# Logic_board.net
KiCad netlist of a schematic drawn in EAGLE
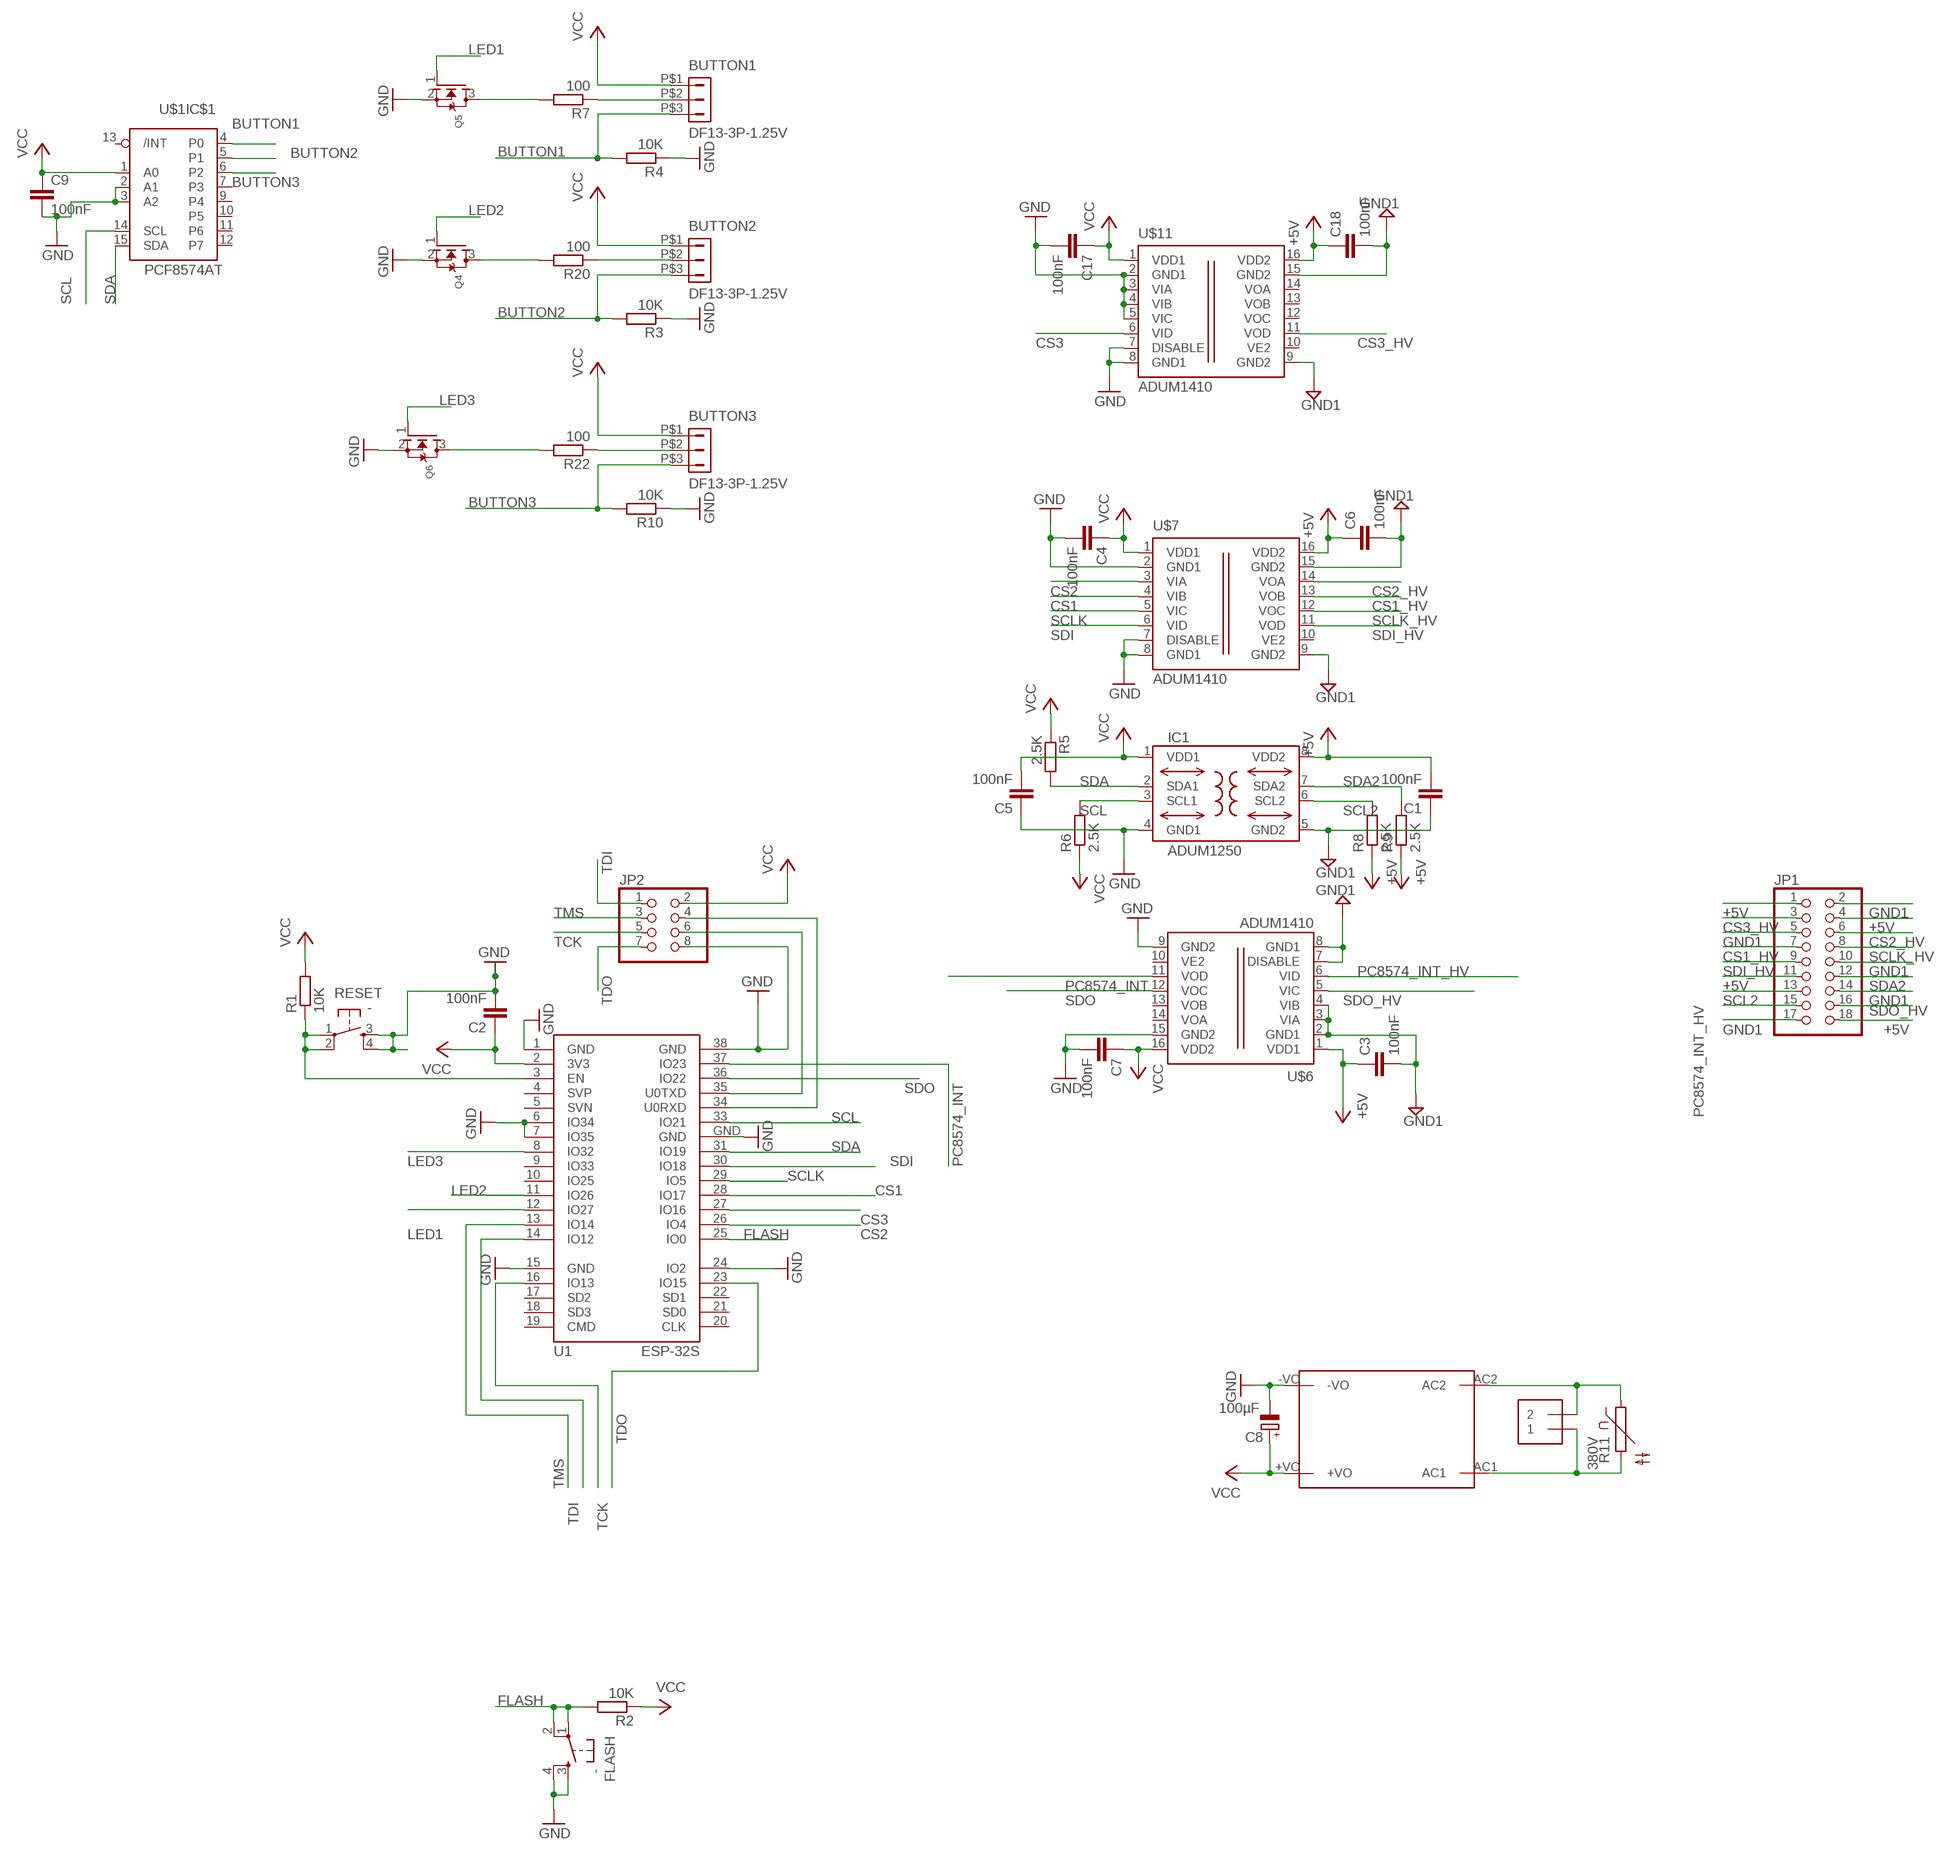
[diagram p0: schematic, sheet 1]

(export (version "E")
  (design (tool "Eeschema 10.0.6"))
  (components
    (comp (ref "BUTTON1")
      (value "DF13-3P-1.25V")
      (footprint "eagle-import:DF13C-3P-1.25V")
      (libsource (lib "eagle-import") (part "DF13-3P-1.25V"))
    )
    (comp (ref "BUTTON2")
      (value "DF13-3P-1.25V")
      (footprint "eagle-import:DF13C-3P-1.25V")
      (libsource (lib "eagle-import") (part "DF13-3P-1.25V"))
    )
    (comp (ref "BUTTON3")
      (value "DF13-3P-1.25V")
      (footprint "eagle-import:DF13C-3P-1.25V")
      (libsource (lib "eagle-import") (part "DF13-3P-1.25V"))
    )
    (comp (ref "C1")
      (value "100nF")
      (footprint "eagle-import:C0805")
      (libsource (lib "eagle-import") (part "C-EUC0805"))
    )
    (comp (ref "C2")
      (value "100nF")
      (footprint "eagle-import:C0805")
      (libsource (lib "eagle-import") (part "C-EUC0805"))
    )
    (comp (ref "C3")
      (value "100nF")
      (footprint "eagle-import:C0805")
      (libsource (lib "eagle-import") (part "C-EUC0805"))
    )
    (comp (ref "C4")
      (value "100nF")
      (footprint "eagle-import:C0805")
      (libsource (lib "eagle-import") (part "C-EUC0805"))
    )
    (comp (ref "C5")
      (value "100nF")
      (footprint "eagle-import:C0805")
      (libsource (lib "eagle-import") (part "C-EUC0805"))
    )
    (comp (ref "C6")
      (value "100nF")
      (footprint "eagle-import:C0805")
      (libsource (lib "eagle-import") (part "C-EUC0805"))
    )
    (comp (ref "C7")
      (value "100nF")
      (footprint "eagle-import:C0805")
      (libsource (lib "eagle-import") (part "C-EUC0805"))
    )
    (comp (ref "C8")
      (value "100µF")
      (footprint "eagle-import:E2,5-6")
      (libsource (lib "eagle-import") (part "CPOL-EUE2.5-6"))
    )
    (comp (ref "C9")
      (value "100nF")
      (footprint "eagle-import:C0805")
      (libsource (lib "eagle-import") (part "C-EUC0805"))
    )
    (comp (ref "C17")
      (value "100nF")
      (footprint "eagle-import:C0805")
      (libsource (lib "eagle-import") (part "C-EUC0805"))
    )
    (comp (ref "C18")
      (value "100nF")
      (footprint "eagle-import:C0805")
      (libsource (lib "eagle-import") (part "C-EUC0805"))
    )
    (comp (ref "FLASH")
      (value "-")
      (footprint "eagle-import:DTSM-6")
      (libsource (lib "eagle-import") (part "DTSM-6"))
    )
    (comp (ref "IC1")
      (value "ADUM1250")
      (footprint "eagle-import:SO8-COOL")
      (libsource (lib "eagle-import") (part "ADUM1250"))
    )
    (comp (ref "J1")
      (value "1X2-3.5MM")
      (footprint "eagle-import:1X2-3.5MM")
      (libsource (lib "eagle-import") (part "1X2-3.5MM"))
    )
    (comp (ref "JP1")
      (value "PINHD-2X9")
      (footprint "eagle-import:2X09")
      (libsource (lib "eagle-import") (part "PINHD-2X9"))
    )
    (comp (ref "JP2")
      (value "PINHD-2X4")
      (footprint "eagle-import:2X04")
      (libsource (lib "eagle-import") (part "PINHD-2X4"))
    )
    (comp (ref "Q4")
      (value "MOSFET-NREFLOW")
      (footprint "eagle-import:SOT23")
      (libsource (lib "eagle-import") (part "MOSFET-NREFLOW"))
    )
    (comp (ref "Q5")
      (value "MOSFET-NREFLOW")
      (footprint "eagle-import:SOT23")
      (libsource (lib "eagle-import") (part "MOSFET-NREFLOW"))
    )
    (comp (ref "Q6")
      (value "MOSFET-NREFLOW")
      (footprint "eagle-import:SOT23")
      (libsource (lib "eagle-import") (part "MOSFET-NREFLOW"))
    )
    (comp (ref "R1")
      (value "10K")
      (footprint "eagle-import:R0805")
      (libsource (lib "eagle-import") (part "R-EU_R0805"))
    )
    (comp (ref "R2")
      (value "10K")
      (footprint "eagle-import:R0805")
      (libsource (lib "eagle-import") (part "R-EU_R0805"))
    )
    (comp (ref "R3")
      (value "10K")
      (footprint "eagle-import:R0805")
      (libsource (lib "eagle-import") (part "R-EU_R0805"))
    )
    (comp (ref "R4")
      (value "10K")
      (footprint "eagle-import:R0805")
      (libsource (lib "eagle-import") (part "R-EU_R0805"))
    )
    (comp (ref "R5")
      (value "2.5K")
      (footprint "eagle-import:R0805")
      (libsource (lib "eagle-import") (part "R-EU_R0805"))
    )
    (comp (ref "R6")
      (value "2.5K")
      (footprint "eagle-import:R0805")
      (libsource (lib "eagle-import") (part "R-EU_R0805"))
    )
    (comp (ref "R7")
      (value "100")
      (footprint "eagle-import:R0805")
      (libsource (lib "eagle-import") (part "R-EU_R0805"))
    )
    (comp (ref "R8")
      (value "2.5K")
      (footprint "eagle-import:R0805")
      (libsource (lib "eagle-import") (part "R-EU_R0805"))
    )
    (comp (ref "R9")
      (value "2.5K")
      (footprint "eagle-import:R0805")
      (libsource (lib "eagle-import") (part "R-EU_R0805"))
    )
    (comp (ref "R10")
      (value "10K")
      (footprint "eagle-import:R0805")
      (libsource (lib "eagle-import") (part "R-EU_R0805"))
    )
    (comp (ref "R11")
      (value "380V")
      (footprint "eagle-import:S14K11")
      (libsource (lib "eagle-import") (part "S14K11"))
    )
    (comp (ref "R20")
      (value "100")
      (footprint "eagle-import:R0805")
      (libsource (lib "eagle-import") (part "R-EU_R0805"))
    )
    (comp (ref "R22")
      (value "100")
      (footprint "eagle-import:R0805")
      (libsource (lib "eagle-import") (part "R-EU_R0805"))
    )
    (comp (ref "RESET")
      (value "-")
      (footprint "eagle-import:DTSM-6")
      (libsource (lib "eagle-import") (part "DTSM-6"))
    )
    (comp (ref "SUPPLY")
      (value "5V")
      (footprint "eagle-import:HLK-PM03")
      (libsource (lib "eagle-import") (part "HLK-PM03"))
    )
    (comp (ref "U$1")
      (value "PCF8574AT")
      (footprint "eagle-import:SO16")
      (libsource (lib "eagle-import") (part "PCF8574AT"))
    )
    (comp (ref "U$6")
      (value "ADUM1410")
      (footprint "eagle-import:SOIC-16")
      (libsource (lib "eagle-import") (part "ADUM1410"))
    )
    (comp (ref "U$7")
      (value "ADUM1410")
      (footprint "eagle-import:SOIC-16")
      (libsource (lib "eagle-import") (part "ADUM1410"))
    )
    (comp (ref "U$11")
      (value "ADUM1410")
      (footprint "eagle-import:SOIC-16")
      (libsource (lib "eagle-import") (part "ADUM1410"))
    )
    (comp (ref "U1")
      (value "ESP-32S")
      (footprint "eagle-import:ESP-32S")
      (libsource (lib "eagle-import") (part "ESP-32S"))
    )
  )
  (nets
    (net (code "1") (name "+5V") (class "Default")
      (node (ref "C1") (pin "2") (pinfunction "2_2") (pintype "passive"))
      (node (ref "C18") (pin "1") (pinfunction "1_1") (pintype "passive"))
      (node (ref "C3") (pin "1") (pinfunction "1_1") (pintype "passive"))
      (node (ref "C6") (pin "1") (pinfunction "1_1") (pintype "passive"))
      (node (ref "IC1") (pin "8") (pinfunction "VDD2_8") (pintype "power_in"))
      (node (ref "JP1") (pin "1") (pinfunction "1_1") (pintype "passive"))
      (node (ref "JP1") (pin "11") (pinfunction "11_11") (pintype "passive"))
      (node (ref "JP1") (pin "18") (pinfunction "18_18") (pintype "passive"))
      (node (ref "JP1") (pin "4") (pinfunction "4_4") (pintype "passive"))
      (node (ref "R8") (pin "1") (pinfunction "1_1") (pintype "passive"))
      (node (ref "R9") (pin "1") (pinfunction "1_1") (pintype "passive"))
      (node (ref "U$11") (pin "16") (pinfunction "VDD2_16") (pintype "input"))
      (node (ref "U$6") (pin "1") (pinfunction "VDD1_1") (pintype "input"))
      (node (ref "U$7") (pin "16") (pinfunction "VDD2_16") (pintype "input"))
    )
    (net (code "2") (name "/BUTTON1") (class "Default")
      (node (ref "BUTTON1") (pin "P$3") (pinfunction "3_P$3") (pintype "passive"))
      (node (ref "R4") (pin "2") (pinfunction "2_2") (pintype "passive"))
      (node (ref "U$1") (pin "4") (pinfunction "P0_4") (pintype "bidirectional"))
    )
    (net (code "3") (name "/BUTTON2") (class "Default")
      (node (ref "BUTTON2") (pin "P$3") (pinfunction "3_P$3") (pintype "passive"))
      (node (ref "R3") (pin "2") (pinfunction "2_2") (pintype "passive"))
      (node (ref "U$1") (pin "5") (pinfunction "P1_5") (pintype "bidirectional"))
    )
    (net (code "4") (name "/BUTTON3") (class "Default")
      (node (ref "BUTTON3") (pin "P$3") (pinfunction "3_P$3") (pintype "passive"))
      (node (ref "R10") (pin "2") (pinfunction "2_2") (pintype "passive"))
      (node (ref "U$1") (pin "6") (pinfunction "P2_6") (pintype "bidirectional"))
    )
    (net (code "5") (name "/CS1") (class "Default")
      (node (ref "U$7") (pin "4") (pinfunction "VIB_4") (pintype "input"))
      (node (ref "U1") (pin "28") (pinfunction "IO17_28") (pintype "bidirectional"))
    )
    (net (code "6") (name "/CS1_HV") (class "Default")
      (node (ref "JP1") (pin "7") (pinfunction "7_7") (pintype "passive"))
      (node (ref "U$7") (pin "13") (pinfunction "VOB_13") (pintype "tri_state"))
    )
    (net (code "7") (name "/CS2") (class "Default")
      (node (ref "U$7") (pin "3") (pinfunction "VIA_3") (pintype "input"))
      (node (ref "U1") (pin "26") (pinfunction "IO4_26") (pintype "bidirectional"))
    )
    (net (code "8") (name "/CS2_HV") (class "Default")
      (node (ref "JP1") (pin "6") (pinfunction "6_6") (pintype "passive"))
      (node (ref "U$7") (pin "14") (pinfunction "VOA_14") (pintype "tri_state"))
    )
    (net (code "9") (name "/CS3") (class "Default")
      (node (ref "U$11") (pin "6") (pinfunction "VID_6") (pintype "input"))
      (node (ref "U1") (pin "27") (pinfunction "IO16_27") (pintype "bidirectional"))
    )
    (net (code "10") (name "/CS3_HV") (class "Default")
      (node (ref "JP1") (pin "3") (pinfunction "3_3") (pintype "passive"))
      (node (ref "U$11") (pin "11") (pinfunction "VOD_11") (pintype "tri_state"))
    )
    (net (code "11") (name "/FLASH") (class "Default")
      (node (ref "FLASH") (pin "1") (pinfunction "1_1") (pintype "passive"))
      (node (ref "FLASH") (pin "2") (pinfunction "2_2") (pintype "passive"))
      (node (ref "R2") (pin "2") (pinfunction "2_2") (pintype "passive"))
      (node (ref "U1") (pin "25") (pinfunction "IO0_25") (pintype "bidirectional"))
    )
    (net (code "12") (name "/LED1") (class "Default")
      (node (ref "Q5") (pin "1") (pinfunction "G_1") (pintype "bidirectional"))
      (node (ref "U1") (pin "12") (pinfunction "IO27_12") (pintype "bidirectional"))
    )
    (net (code "13") (name "/LED2") (class "Default")
      (node (ref "Q4") (pin "1") (pinfunction "G_1") (pintype "bidirectional"))
      (node (ref "U1") (pin "11") (pinfunction "IO26_11") (pintype "bidirectional"))
    )
    (net (code "14") (name "/LED3") (class "Default")
      (node (ref "Q6") (pin "1") (pinfunction "G_1") (pintype "bidirectional"))
      (node (ref "U1") (pin "8") (pinfunction "IO32_8") (pintype "bidirectional"))
    )
    (net (code "15") (name "/PC8574_INT") (class "Default")
      (node (ref "U$6") (pin "11") (pinfunction "VOD_11") (pintype "tri_state"))
      (node (ref "U1") (pin "37") (pinfunction "IO23_37") (pintype "bidirectional"))
    )
    (net (code "16") (name "/PC8574_INT_HV") (class "Default")
      (node (ref "JP1") (pin "15") (pinfunction "15_15") (pintype "passive"))
      (node (ref "U$6") (pin "6") (pinfunction "VID_6") (pintype "input"))
    )
    (net (code "17") (name "/SCL") (class "Default")
      (node (ref "IC1") (pin "3") (pinfunction "SCL1_3") (pintype "bidirectional"))
      (node (ref "R6") (pin "2") (pinfunction "2_2") (pintype "passive"))
      (node (ref "U$1") (pin "14") (pinfunction "SCL_14") (pintype "input"))
      (node (ref "U1") (pin "33") (pinfunction "IO21_33") (pintype "bidirectional"))
    )
    (net (code "18") (name "/SCL2") (class "Default")
      (node (ref "IC1") (pin "6") (pinfunction "SCL2_6") (pintype "bidirectional"))
      (node (ref "JP1") (pin "13") (pinfunction "13_13") (pintype "passive"))
      (node (ref "R8") (pin "2") (pinfunction "2_2") (pintype "passive"))
    )
    (net (code "19") (name "/SCLK") (class "Default")
      (node (ref "U$7") (pin "5") (pinfunction "VIC_5") (pintype "input"))
      (node (ref "U1") (pin "29") (pinfunction "IO5_29") (pintype "bidirectional"))
    )
    (net (code "20") (name "/SCLK_HV") (class "Default")
      (node (ref "JP1") (pin "8") (pinfunction "8_8") (pintype "passive"))
      (node (ref "U$7") (pin "12") (pinfunction "VOC_12") (pintype "tri_state"))
    )
    (net (code "21") (name "/SDA") (class "Default")
      (node (ref "IC1") (pin "2") (pinfunction "SDA1_2") (pintype "bidirectional"))
      (node (ref "R5") (pin "2") (pinfunction "2_2") (pintype "passive"))
      (node (ref "U$1") (pin "15") (pinfunction "SDA_15") (pintype "bidirectional"))
      (node (ref "U1") (pin "31") (pinfunction "IO19_31") (pintype "bidirectional"))
    )
    (net (code "22") (name "/SDA2") (class "Default")
      (node (ref "IC1") (pin "7") (pinfunction "SDA2_7") (pintype "bidirectional"))
      (node (ref "JP1") (pin "12") (pinfunction "12_12") (pintype "passive"))
      (node (ref "R9") (pin "2") (pinfunction "2_2") (pintype "passive"))
    )
    (net (code "23") (name "/SDI") (class "Default")
      (node (ref "U$7") (pin "6") (pinfunction "VID_6") (pintype "input"))
      (node (ref "U1") (pin "30") (pinfunction "IO18_30") (pintype "bidirectional"))
    )
    (net (code "24") (name "/SDI_HV") (class "Default")
      (node (ref "JP1") (pin "9") (pinfunction "9_9") (pintype "passive"))
      (node (ref "U$7") (pin "11") (pinfunction "VOD_11") (pintype "tri_state"))
    )
    (net (code "25") (name "/SDO") (class "Default")
      (node (ref "U$6") (pin "12") (pinfunction "VOC_12") (pintype "tri_state"))
      (node (ref "U1") (pin "36") (pinfunction "IO22_36") (pintype "bidirectional"))
    )
    (net (code "26") (name "/SDO_HV") (class "Default")
      (node (ref "JP1") (pin "16") (pinfunction "16_16") (pintype "passive"))
      (node (ref "U$6") (pin "5") (pinfunction "VIC_5") (pintype "input"))
    )
    (net (code "27") (name "/TCK") (class "Default")
      (node (ref "JP2") (pin "5") (pinfunction "5_5") (pintype "passive"))
      (node (ref "U1") (pin "16") (pinfunction "IO13_16") (pintype "bidirectional"))
    )
    (net (code "28") (name "/TDI") (class "Default")
      (node (ref "JP2") (pin "1") (pinfunction "1_1") (pintype "passive"))
      (node (ref "U1") (pin "14") (pinfunction "IO12_14") (pintype "bidirectional"))
    )
    (net (code "29") (name "/TDO") (class "Default")
      (node (ref "JP2") (pin "7") (pinfunction "7_7") (pintype "passive"))
      (node (ref "U1") (pin "23") (pinfunction "IO15_23") (pintype "bidirectional"))
    )
    (net (code "30") (name "/TMS") (class "Default")
      (node (ref "JP2") (pin "3") (pinfunction "3_3") (pintype "passive"))
      (node (ref "U1") (pin "13") (pinfunction "IO14_13") (pintype "bidirectional"))
    )
    (net (code "31") (name "GND") (class "Default")
      (node (ref "C17") (pin "2") (pinfunction "2_2") (pintype "passive"))
      (node (ref "C2") (pin "2") (pinfunction "2_2") (pintype "passive"))
      (node (ref "C4") (pin "2") (pinfunction "2_2") (pintype "passive"))
      (node (ref "C5") (pin "1") (pinfunction "1_1") (pintype "passive"))
      (node (ref "C7") (pin "2") (pinfunction "2_2") (pintype "passive"))
      (node (ref "C8") (pin "-") (pinfunction "-_-") (pintype "passive"))
      (node (ref "C9") (pin "2") (pinfunction "2_2") (pintype "passive"))
      (node (ref "FLASH") (pin "3") (pinfunction "3_3") (pintype "passive"))
      (node (ref "FLASH") (pin "4") (pinfunction "4_4") (pintype "passive"))
      (node (ref "IC1") (pin "4") (pinfunction "GND1_4") (pintype "power_in"))
      (node (ref "JP2") (pin "8") (pinfunction "8_8") (pintype "passive"))
      (node (ref "Q4") (pin "2") (pinfunction "S_2") (pintype "bidirectional"))
      (node (ref "Q5") (pin "2") (pinfunction "S_2") (pintype "bidirectional"))
      (node (ref "Q6") (pin "2") (pinfunction "S_2") (pintype "bidirectional"))
      (node (ref "R10") (pin "1") (pinfunction "1_1") (pintype "passive"))
      (node (ref "R3") (pin "1") (pinfunction "1_1") (pintype "passive"))
      (node (ref "R4") (pin "1") (pinfunction "1_1") (pintype "passive"))
      (node (ref "RESET") (pin "3") (pinfunction "3_3") (pintype "passive"))
      (node (ref "RESET") (pin "4") (pinfunction "4_4") (pintype "passive"))
      (node (ref "SUPPLY") (pin "-VO") (pinfunction "-VO_-VO") (pintype "bidirectional"))
      (node (ref "U$1") (pin "2") (pinfunction "A1_2") (pintype "input"))
      (node (ref "U$1") (pin "3") (pinfunction "A2_3") (pintype "input"))
      (node (ref "U$11") (pin "2") (pinfunction "GND1_2") (pintype "input"))
      (node (ref "U$11") (pin "3") (pinfunction "VIA_3") (pintype "input"))
      (node (ref "U$11") (pin "4") (pinfunction "VIB_4") (pintype "input"))
      (node (ref "U$11") (pin "5") (pinfunction "VIC_5") (pintype "input"))
      (node (ref "U$11") (pin "7") (pinfunction "DISABLE_7") (pintype "input"))
      (node (ref "U$11") (pin "8") (pinfunction "GND1_8") (pintype "input"))
      (node (ref "U$6") (pin "15") (pinfunction "GND2_15") (pintype "input"))
      (node (ref "U$6") (pin "9") (pinfunction "GND2_9") (pintype "input"))
      (node (ref "U$7") (pin "2") (pinfunction "GND1_2") (pintype "input"))
      (node (ref "U$7") (pin "7") (pinfunction "DISABLE_7") (pintype "input"))
      (node (ref "U$7") (pin "8") (pinfunction "GND1_8") (pintype "input"))
      (node (ref "U1") (pin "1") (pinfunction "GND_1") (pintype "power_in"))
      (node (ref "U1") (pin "15") (pinfunction "GND_15") (pintype "power_in"))
      (node (ref "U1") (pin "24") (pinfunction "IO2_24") (pintype "bidirectional"))
      (node (ref "U1") (pin "38") (pinfunction "GND_38") (pintype "power_in"))
      (node (ref "U1") (pin "6") (pinfunction "IO34_6") (pintype "bidirectional"))
      (node (ref "U1") (pin "7") (pinfunction "IO35_7") (pintype "bidirectional"))
      (node (ref "U1") (pin "GND") (pinfunction "GND_GND") (pintype "power_in"))
    )
    (net (code "32") (name "GND1") (class "Default")
      (node (ref "C1") (pin "1") (pinfunction "1_1") (pintype "passive"))
      (node (ref "C18") (pin "2") (pinfunction "2_2") (pintype "passive"))
      (node (ref "C3") (pin "2") (pinfunction "2_2") (pintype "passive"))
      (node (ref "C6") (pin "2") (pinfunction "2_2") (pintype "passive"))
      (node (ref "IC1") (pin "5") (pinfunction "GND2_5") (pintype "power_in"))
      (node (ref "JP1") (pin "10") (pinfunction "10_10") (pintype "passive"))
      (node (ref "JP1") (pin "14") (pinfunction "14_14") (pintype "passive"))
      (node (ref "JP1") (pin "17") (pinfunction "17_17") (pintype "passive"))
      (node (ref "JP1") (pin "2") (pinfunction "2_2") (pintype "passive"))
      (node (ref "JP1") (pin "5") (pinfunction "5_5") (pintype "passive"))
      (node (ref "U$11") (pin "15") (pinfunction "GND2_15") (pintype "input"))
      (node (ref "U$11") (pin "9") (pinfunction "GND2_9") (pintype "input"))
      (node (ref "U$6") (pin "2") (pinfunction "GND1_2") (pintype "input"))
      (node (ref "U$6") (pin "3") (pinfunction "VIA_3") (pintype "input"))
      (node (ref "U$6") (pin "4") (pinfunction "VIB_4") (pintype "input"))
      (node (ref "U$6") (pin "7") (pinfunction "DISABLE_7") (pintype "input"))
      (node (ref "U$6") (pin "8") (pinfunction "GND1_8") (pintype "input"))
      (node (ref "U$7") (pin "15") (pinfunction "GND2_15") (pintype "input"))
      (node (ref "U$7") (pin "9") (pinfunction "GND2_9") (pintype "input"))
    )
    (net (code "33") (name "Net-(BUTTON1-2)") (class "Default")
      (node (ref "BUTTON1") (pin "P$2") (pinfunction "2_P$2") (pintype "passive"))
      (node (ref "R7") (pin "1") (pinfunction "1_1") (pintype "passive"))
    )
    (net (code "34") (name "Net-(BUTTON2-2)") (class "Default")
      (node (ref "BUTTON2") (pin "P$2") (pinfunction "2_P$2") (pintype "passive"))
      (node (ref "R20") (pin "1") (pinfunction "1_1") (pintype "passive"))
    )
    (net (code "35") (name "Net-(BUTTON3-2)") (class "Default")
      (node (ref "BUTTON3") (pin "P$2") (pinfunction "2_P$2") (pintype "passive"))
      (node (ref "R22") (pin "1") (pinfunction "1_1") (pintype "passive"))
    )
    (net (code "36") (name "Net-(J1-Pad1)") (class "Default")
      (node (ref "J1") (pin "1") (pinfunction "1_1") (pintype "passive"))
      (node (ref "R11") (pin "2") (pinfunction "2_2") (pintype "passive"))
      (node (ref "SUPPLY") (pin "AC1") (pinfunction "AC1_AC1") (pintype "bidirectional"))
    )
    (net (code "37") (name "Net-(J1-Pad2)") (class "Default")
      (node (ref "J1") (pin "2") (pinfunction "2_2") (pintype "passive"))
      (node (ref "R11") (pin "1") (pinfunction "1_1") (pintype "passive"))
      (node (ref "SUPPLY") (pin "AC2") (pinfunction "AC2_AC2") (pintype "bidirectional"))
    )
    (net (code "38") (name "Net-(Q4-D)") (class "Default")
      (node (ref "Q4") (pin "3") (pinfunction "D_3") (pintype "bidirectional"))
      (node (ref "R20") (pin "2") (pinfunction "2_2") (pintype "passive"))
    )
    (net (code "39") (name "Net-(Q5-D)") (class "Default")
      (node (ref "Q5") (pin "3") (pinfunction "D_3") (pintype "bidirectional"))
      (node (ref "R7") (pin "2") (pinfunction "2_2") (pintype "passive"))
    )
    (net (code "40") (name "Net-(Q6-D)") (class "Default")
      (node (ref "Q6") (pin "3") (pinfunction "D_3") (pintype "bidirectional"))
      (node (ref "R22") (pin "2") (pinfunction "2_2") (pintype "passive"))
    )
    (net (code "41") (name "Net-(U1-EN)") (class "Default")
      (node (ref "R1") (pin "1") (pinfunction "1_1") (pintype "passive"))
      (node (ref "RESET") (pin "1") (pinfunction "1_1") (pintype "passive"))
      (node (ref "RESET") (pin "2") (pinfunction "2_2") (pintype "passive"))
      (node (ref "U1") (pin "3") (pinfunction "EN_3") (pintype "input"))
    )
    (net (code "42") (name "Net-(U1-U0RXD)") (class "Default")
      (node (ref "JP2") (pin "4") (pinfunction "4_4") (pintype "passive"))
      (node (ref "U1") (pin "34") (pinfunction "U0RXD_34") (pintype "bidirectional"))
    )
    (net (code "43") (name "Net-(U1-U0TXD)") (class "Default")
      (node (ref "JP2") (pin "6") (pinfunction "6_6") (pintype "passive"))
      (node (ref "U1") (pin "35") (pinfunction "U0TXD_35") (pintype "bidirectional"))
    )
    (net (code "44") (name "VCC") (class "Default")
      (node (ref "BUTTON1") (pin "P$1") (pinfunction "1_P$1") (pintype "passive"))
      (node (ref "BUTTON2") (pin "P$1") (pinfunction "1_P$1") (pintype "passive"))
      (node (ref "BUTTON3") (pin "P$1") (pinfunction "1_P$1") (pintype "passive"))
      (node (ref "C17") (pin "1") (pinfunction "1_1") (pintype "passive"))
      (node (ref "C2") (pin "1") (pinfunction "1_1") (pintype "passive"))
      (node (ref "C4") (pin "1") (pinfunction "1_1") (pintype "passive"))
      (node (ref "C5") (pin "2") (pinfunction "2_2") (pintype "passive"))
      (node (ref "C7") (pin "1") (pinfunction "1_1") (pintype "passive"))
      (node (ref "C8") (pin "+") (pinfunction "+_+") (pintype "passive"))
      (node (ref "C9") (pin "1") (pinfunction "1_1") (pintype "passive"))
      (node (ref "IC1") (pin "1") (pinfunction "VDD1_1") (pintype "power_in"))
      (node (ref "JP2") (pin "2") (pinfunction "2_2") (pintype "passive"))
      (node (ref "R1") (pin "2") (pinfunction "2_2") (pintype "passive"))
      (node (ref "R2") (pin "1") (pinfunction "1_1") (pintype "passive"))
      (node (ref "R5") (pin "1") (pinfunction "1_1") (pintype "passive"))
      (node (ref "R6") (pin "1") (pinfunction "1_1") (pintype "passive"))
      (node (ref "SUPPLY") (pin "+VO") (pinfunction "+VO_+VO") (pintype "bidirectional"))
      (node (ref "U$1") (pin "1") (pinfunction "A0_1") (pintype "input"))
      (node (ref "U$11") (pin "1") (pinfunction "VDD1_1") (pintype "input"))
      (node (ref "U$6") (pin "16") (pinfunction "VDD2_16") (pintype "input"))
      (node (ref "U$7") (pin "1") (pinfunction "VDD1_1") (pintype "input"))
      (node (ref "U1") (pin "2") (pinfunction "3V3_2") (pintype "power_in"))
    )
    (net (code "45") (name "unconnected-(U$1A-P3-Pad7)") (class "Default")
      (node (ref "U$1") (pin "7") (pinfunction "P3_7") (pintype "bidirectional"))
    )
    (net (code "46") (name "unconnected-(U$1A-P4-Pad9)") (class "Default")
      (node (ref "U$1") (pin "9") (pinfunction "P4_9") (pintype "bidirectional"))
    )
    (net (code "47") (name "unconnected-(U$1A-P5-Pad10)") (class "Default")
      (node (ref "U$1") (pin "10") (pinfunction "P5_10") (pintype "bidirectional"))
    )
    (net (code "48") (name "unconnected-(U$1A-P6-Pad11)") (class "Default")
      (node (ref "U$1") (pin "11") (pinfunction "P6_11") (pintype "bidirectional"))
    )
    (net (code "49") (name "unconnected-(U$1A-P7-Pad12)") (class "Default")
      (node (ref "U$1") (pin "12") (pinfunction "P7_12") (pintype "bidirectional"))
    )
    (net (code "50") (name "unconnected-(U$1A-{slash}INT-Pad13)") (class "Default")
      (node (ref "U$1") (pin "13") (pinfunction "/INT_13") (pintype "output"))
    )
    (net (code "51") (name "unconnected-(U$6-VE2-Pad10)") (class "Default")
      (node (ref "U$6") (pin "10") (pinfunction "VE2_10") (pintype "input"))
    )
    (net (code "52") (name "unconnected-(U$6-VOA-Pad14)") (class "Default")
      (node (ref "U$6") (pin "14") (pinfunction "VOA_14") (pintype "tri_state"))
    )
    (net (code "53") (name "unconnected-(U$6-VOB-Pad13)") (class "Default")
      (node (ref "U$6") (pin "13") (pinfunction "VOB_13") (pintype "tri_state"))
    )
    (net (code "54") (name "unconnected-(U$7-VE2-Pad10)") (class "Default")
      (node (ref "U$7") (pin "10") (pinfunction "VE2_10") (pintype "input"))
    )
    (net (code "55") (name "unconnected-(U$11-VE2-Pad10)") (class "Default")
      (node (ref "U$11") (pin "10") (pinfunction "VE2_10") (pintype "input"))
    )
    (net (code "56") (name "unconnected-(U$11-VOA-Pad14)") (class "Default")
      (node (ref "U$11") (pin "14") (pinfunction "VOA_14") (pintype "tri_state"))
    )
    (net (code "57") (name "unconnected-(U$11-VOB-Pad13)") (class "Default")
      (node (ref "U$11") (pin "13") (pinfunction "VOB_13") (pintype "tri_state"))
    )
    (net (code "58") (name "unconnected-(U$11-VOC-Pad12)") (class "Default")
      (node (ref "U$11") (pin "12") (pinfunction "VOC_12") (pintype "tri_state"))
    )
    (net (code "59") (name "unconnected-(U1-CLK-Pad20)") (class "Default")
      (node (ref "U1") (pin "20") (pinfunction "CLK_20") (pintype "bidirectional"))
    )
    (net (code "60") (name "unconnected-(U1-CMD-Pad19)") (class "Default")
      (node (ref "U1") (pin "19") (pinfunction "CMD_19") (pintype "bidirectional"))
    )
    (net (code "61") (name "unconnected-(U1-IO25-Pad10)") (class "Default")
      (node (ref "U1") (pin "10") (pinfunction "IO25_10") (pintype "bidirectional"))
    )
    (net (code "62") (name "unconnected-(U1-IO33-Pad9)") (class "Default")
      (node (ref "U1") (pin "9") (pinfunction "IO33_9") (pintype "bidirectional"))
    )
    (net (code "63") (name "unconnected-(U1-SD0-Pad21)") (class "Default")
      (node (ref "U1") (pin "21") (pinfunction "SD0_21") (pintype "bidirectional"))
    )
    (net (code "64") (name "unconnected-(U1-SD1-Pad22)") (class "Default")
      (node (ref "U1") (pin "22") (pinfunction "SD1_22") (pintype "bidirectional"))
    )
    (net (code "65") (name "unconnected-(U1-SD2-Pad17)") (class "Default")
      (node (ref "U1") (pin "17") (pinfunction "SD2_17") (pintype "bidirectional"))
    )
    (net (code "66") (name "unconnected-(U1-SD3-Pad18)") (class "Default")
      (node (ref "U1") (pin "18") (pinfunction "SD3_18") (pintype "bidirectional"))
    )
    (net (code "67") (name "unconnected-(U1-SVN-Pad5)") (class "Default")
      (node (ref "U1") (pin "5") (pinfunction "SVN_5") (pintype "bidirectional"))
    )
    (net (code "68") (name "unconnected-(U1-SVP-Pad4)") (class "Default")
      (node (ref "U1") (pin "4") (pinfunction "SVP_4") (pintype "bidirectional"))
    )
  )
)
